# project2.net
KiCad netlist of a schematic drawn in EAGLE
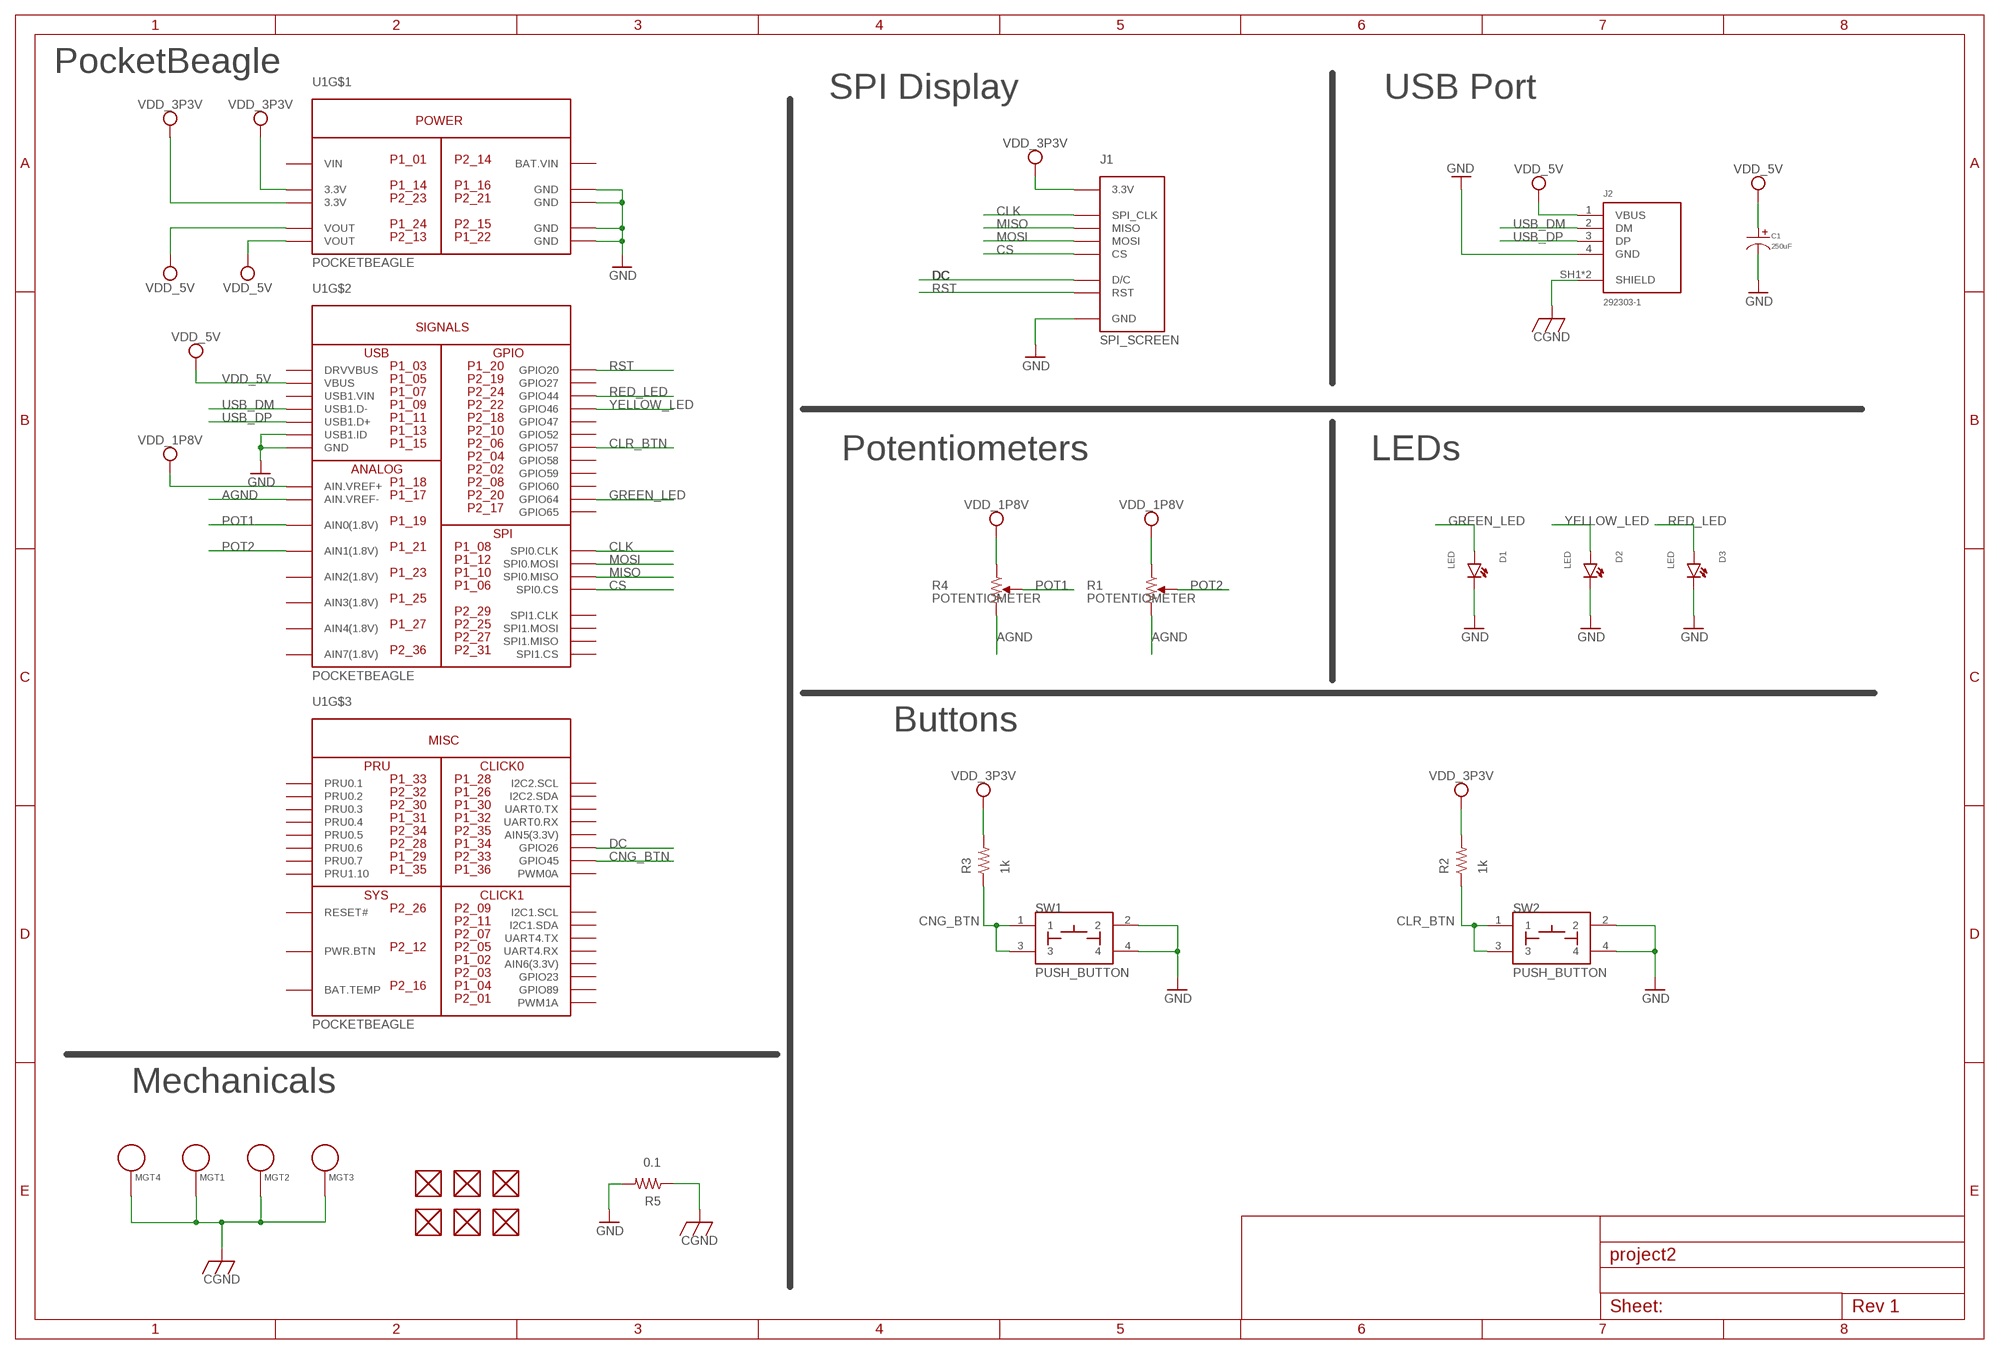
[diagram p0: schematic, sheet 1]

(export (version "E")
  (design (tool "Eeschema 10.0.6"))
  (components
    (comp (ref "C1")
      (value "250uF")
      (footprint "eagle-import:CP10MM")
      (libsource (lib "eagle-import") (part "CAPACITOR_P_10MM"))
    )
    (comp (ref "D1")
      (value "LED")
      (footprint "eagle-import:EIA-STD")
      (libsource (lib "eagle-import") (part "LED"))
    )
    (comp (ref "D2")
      (value "LED")
      (footprint "eagle-import:EIA-STD")
      (libsource (lib "eagle-import") (part "LED"))
    )
    (comp (ref "D3")
      (value "LED")
      (footprint "eagle-import:EIA-STD")
      (libsource (lib "eagle-import") (part "LED"))
    )
    (comp (ref "FUD1")
      (value "FIDUCIAL")
      (footprint "eagle-import:FIDUCIAL_40MIL")
      (libsource (lib "eagle-import") (part "FIDUCIAL"))
    )
    (comp (ref "FUD2")
      (value "FIDUCIAL")
      (footprint "eagle-import:FIDUCIAL_40MIL")
      (libsource (lib "eagle-import") (part "FIDUCIAL"))
    )
    (comp (ref "FUD3")
      (value "FIDUCIAL")
      (footprint "eagle-import:FIDUCIAL_40MIL")
      (libsource (lib "eagle-import") (part "FIDUCIAL"))
    )
    (comp (ref "FUD4")
      (value "FIDUCIAL")
      (footprint "eagle-import:FIDUCIAL_40MIL")
      (libsource (lib "eagle-import") (part "FIDUCIAL"))
    )
    (comp (ref "FUD5")
      (value "FIDUCIAL")
      (footprint "eagle-import:FIDUCIAL_40MIL")
      (libsource (lib "eagle-import") (part "FIDUCIAL"))
    )
    (comp (ref "FUD6")
      (value "FIDUCIAL")
      (footprint "eagle-import:FIDUCIAL_40MIL")
      (libsource (lib "eagle-import") (part "FIDUCIAL"))
    )
    (comp (ref "J1")
      (value "SPI_SCREEN")
      (footprint "eagle-import:SPI_SCREEN")
      (libsource (lib "eagle-import") (part "SPI_SCREEN"))
    )
    (comp (ref "J2")
      (value "292303-1")
      (footprint "eagle-import:TE_292303-1")
      (fields (field (name "MF") "TE Connectivity"))
      (libsource (lib "eagle-import") (part "292303-1"))
    )
    (comp (ref "MGT1")
      (value "MOUNTING_HOLE")
      (footprint "eagle-import:MOUNTING_HOLE")
      (libsource (lib "eagle-import") (part "MOUNTING_HOLE"))
    )
    (comp (ref "MGT2")
      (value "MOUNTING_HOLE")
      (footprint "eagle-import:MOUNTING_HOLE")
      (libsource (lib "eagle-import") (part "MOUNTING_HOLE"))
    )
    (comp (ref "MGT3")
      (value "MOUNTING_HOLE")
      (footprint "eagle-import:MOUNTING_HOLE")
      (libsource (lib "eagle-import") (part "MOUNTING_HOLE"))
    )
    (comp (ref "MGT4")
      (value "MOUNTING_HOLE")
      (footprint "eagle-import:MOUNTING_HOLE")
      (libsource (lib "eagle-import") (part "MOUNTING_HOLE"))
    )
    (comp (ref "R1")
      (value "POTENTIOMETER")
      (footprint "eagle-import:POT-PO90S")
      (libsource (lib "eagle-import") (part "POTENTIOMETER"))
    )
    (comp (ref "R2")
      (value "1k")
      (footprint "eagle-import:R0603")
      (libsource (lib "eagle-import") (part "R_R0603"))
    )
    (comp (ref "R3")
      (value "1k")
      (footprint "eagle-import:R0603")
      (libsource (lib "eagle-import") (part "R_R0603"))
    )
    (comp (ref "R4")
      (value "POTENTIOMETER")
      (footprint "eagle-import:POT-PO90S")
      (libsource (lib "eagle-import") (part "POTENTIOMETER"))
    )
    (comp (ref "R5")
      (value "0.1")
      (footprint "eagle-import:R0603")
      (libsource (lib "eagle-import") (part "R_R0603"))
    )
    (comp (ref "SW1")
      (value "PUSH_BUTTON")
      (footprint "eagle-import:BUTTON_12.5MM")
      (libsource (lib "eagle-import") (part "PUSH_BUTTON"))
    )
    (comp (ref "SW2")
      (value "PUSH_BUTTON")
      (footprint "eagle-import:BUTTON_12.5MM")
      (libsource (lib "eagle-import") (part "PUSH_BUTTON"))
    )
    (comp (ref "U1")
      (value "POCKETBEAGLE")
      (footprint "eagle-import:POCKETBEAGLE")
      (libsource (lib "eagle-import") (part "POCKETBEAGLE"))
    )
  )
  (nets
    (net (code "1") (name "/AGND") (class "Default")
      (node (ref "R1") (pin "CW") (pinfunction "CW_CW") (pintype "passive"))
      (node (ref "R4") (pin "CW") (pinfunction "CW_CW") (pintype "passive"))
      (node (ref "U1") (pin "17@P1") (pinfunction "AIN.VREF-_17@P1") (pintype "input"))
    )
    (net (code "2") (name "/BAT.VIN") (class "Default")
      (node (ref "U1") (pin "14@P2") (pinfunction "BAT.VIN_14@P2") (pintype "power_in"))
    )
    (net (code "3") (name "/CLK") (class "Default")
      (node (ref "J1") (pin "4@JP2") (pinfunction "SPI_CLK_4@JP2") (pintype "bidirectional"))
      (node (ref "U1") (pin "8@P1") (pinfunction "SPI0.CLK_8@P1") (pintype "bidirectional"))
    )
    (net (code "4") (name "/CLR_BTN") (class "Default")
      (node (ref "R2") (pin "1") (pinfunction "1_1") (pintype "passive"))
      (node (ref "SW2") (pin "1") (pinfunction "1_1") (pintype "bidirectional"))
      (node (ref "SW2") (pin "3") (pinfunction "3_3") (pintype "bidirectional"))
      (node (ref "U1") (pin "6@P2") (pinfunction "GPIO57_6@P2") (pintype "bidirectional"))
    )
    (net (code "5") (name "/CNG_BTN") (class "Default")
      (node (ref "R3") (pin "1") (pinfunction "1_1") (pintype "passive"))
      (node (ref "SW1") (pin "1") (pinfunction "1_1") (pintype "bidirectional"))
      (node (ref "SW1") (pin "3") (pinfunction "3_3") (pintype "bidirectional"))
      (node (ref "U1") (pin "33@P2") (pinfunction "GPIO45_33@P2") (pintype "bidirectional"))
    )
    (net (code "6") (name "/CS") (class "Default")
      (node (ref "J1") (pin "7@JP2") (pinfunction "CS_7@JP2") (pintype "bidirectional"))
      (node (ref "U1") (pin "6@P1") (pinfunction "SPI0.CS_6@P1") (pintype "bidirectional"))
    )
    (net (code "7") (name "/DC") (class "Default")
      (node (ref "J1") (pin "8@JP2") (pinfunction "D/C_8@JP2") (pintype "bidirectional"))
      (node (ref "U1") (pin "34@P1") (pinfunction "GPIO26_34@P1") (pintype "bidirectional"))
    )
    (net (code "8") (name "/GREEN_LED") (class "Default")
      (node (ref "D1") (pin "ANODE") (pinfunction "ANODE_ANODE") (pintype "bidirectional"))
      (node (ref "U1") (pin "20@P2") (pinfunction "GPIO64_20@P2") (pintype "bidirectional"))
    )
    (net (code "9") (name "/MISO") (class "Default")
      (node (ref "J1") (pin "5@JP2") (pinfunction "MISO_5@JP2") (pintype "bidirectional"))
      (node (ref "U1") (pin "10@P1") (pinfunction "SPI0.MISO_10@P1") (pintype "bidirectional"))
    )
    (net (code "10") (name "/MOSI") (class "Default")
      (node (ref "J1") (pin "6@JP2") (pinfunction "MOSI_6@JP2") (pintype "bidirectional"))
      (node (ref "U1") (pin "12@P1") (pinfunction "SPI0.MOSI_12@P1") (pintype "bidirectional"))
    )
    (net (code "11") (name "/POT1") (class "Default")
      (node (ref "R4") (pin "S") (pinfunction "S_S") (pintype "bidirectional"))
      (node (ref "U1") (pin "19@P1") (pinfunction "AIN0(1.8V)_19@P1") (pintype "input"))
    )
    (net (code "12") (name "/POT2") (class "Default")
      (node (ref "R1") (pin "S") (pinfunction "S_S") (pintype "bidirectional"))
      (node (ref "U1") (pin "21@P1") (pinfunction "AIN1(1.8V)_21@P1") (pintype "input"))
    )
    (net (code "13") (name "/RED_LED") (class "Default")
      (node (ref "D3") (pin "ANODE") (pinfunction "ANODE_ANODE") (pintype "bidirectional"))
      (node (ref "U1") (pin "24@P2") (pinfunction "GPIO44_24@P2") (pintype "bidirectional"))
    )
    (net (code "14") (name "/RST") (class "Default")
      (node (ref "J1") (pin "9@JP2") (pinfunction "RST_9@JP2") (pintype "bidirectional"))
      (node (ref "U1") (pin "20@P1") (pinfunction "GPIO20_20@P1") (pintype "bidirectional"))
    )
    (net (code "15") (name "/USB_DM") (class "Default")
      (node (ref "J2") (pin "2") (pinfunction "DM_2") (pintype "passive"))
      (node (ref "U1") (pin "9@P1") (pinfunction "USB1.D-_9@P1") (pintype "bidirectional"))
    )
    (net (code "16") (name "/USB_DP") (class "Default")
      (node (ref "J2") (pin "3") (pinfunction "DP_3") (pintype "passive"))
      (node (ref "U1") (pin "11@P1") (pinfunction "USB1.D+_11@P1") (pintype "bidirectional"))
    )
    (net (code "17") (name "/VIN") (class "Default")
      (node (ref "U1") (pin "1@P1") (pinfunction "VIN_1@P1") (pintype "power_in"))
    )
    (net (code "18") (name "/YELLOW_LED") (class "Default")
      (node (ref "D2") (pin "ANODE") (pinfunction "ANODE_ANODE") (pintype "bidirectional"))
      (node (ref "U1") (pin "22@P2") (pinfunction "GPIO46_22@P2") (pintype "bidirectional"))
    )
    (net (code "19") (name "CGND") (class "Default")
      (node (ref "J2") (pin "SH1") (pinfunction "SHIELD_SH1") (pintype "passive"))
      (node (ref "J2") (pin "SH2") (pinfunction "SHIELD_SH2") (pintype "passive"))
      (node (ref "MGT1") (pin "P$1") (pinfunction "P$1_P$1") (pintype "bidirectional"))
      (node (ref "MGT2") (pin "P$1") (pinfunction "P$1_P$1") (pintype "bidirectional"))
      (node (ref "MGT3") (pin "P$1") (pinfunction "P$1_P$1") (pintype "bidirectional"))
      (node (ref "MGT4") (pin "P$1") (pinfunction "P$1_P$1") (pintype "bidirectional"))
      (node (ref "R5") (pin "1") (pinfunction "1_1") (pintype "passive"))
    )
    (net (code "20") (name "GND") (class "Default")
      (node (ref "C1") (pin "P$2") (pinfunction "P$2_P$2") (pintype "passive"))
      (node (ref "D1") (pin "CATHODE") (pinfunction "CATHODE_CATHODE") (pintype "bidirectional"))
      (node (ref "D2") (pin "CATHODE") (pinfunction "CATHODE_CATHODE") (pintype "bidirectional"))
      (node (ref "D3") (pin "CATHODE") (pinfunction "CATHODE_CATHODE") (pintype "bidirectional"))
      (node (ref "J1") (pin "1@JP2") (pinfunction "GND_1@JP2") (pintype "bidirectional"))
      (node (ref "J2") (pin "4") (pinfunction "GND_4") (pintype "passive"))
      (node (ref "R5") (pin "2") (pinfunction "2_2") (pintype "passive"))
      (node (ref "SW1") (pin "2") (pinfunction "2_2") (pintype "bidirectional"))
      (node (ref "SW1") (pin "4") (pinfunction "4_4") (pintype "bidirectional"))
      (node (ref "SW2") (pin "2") (pinfunction "2_2") (pintype "bidirectional"))
      (node (ref "SW2") (pin "4") (pinfunction "4_4") (pintype "bidirectional"))
      (node (ref "U1") (pin "13@P1") (pinfunction "USB1.ID_13@P1") (pintype "bidirectional"))
      (node (ref "U1") (pin "15@P1") (pinfunction "GND_15@P1") (pintype "bidirectional"))
      (node (ref "U1") (pin "15@P2") (pinfunction "GND_15@P2") (pintype "power_in"))
      (node (ref "U1") (pin "16@P1") (pinfunction "GND_16@P1") (pintype "power_in"))
      (node (ref "U1") (pin "21@P2") (pinfunction "GND_21@P2") (pintype "power_in"))
      (node (ref "U1") (pin "22@P1") (pinfunction "GND_22@P1") (pintype "power_in"))
    )
    (net (code "21") (name "VDD_1P8V") (class "Default")
      (node (ref "R1") (pin "CCW") (pinfunction "CCW_CCW") (pintype "passive"))
      (node (ref "R4") (pin "CCW") (pinfunction "CCW_CCW") (pintype "passive"))
      (node (ref "U1") (pin "18@P1") (pinfunction "AIN.VREF+_18@P1") (pintype "input"))
    )
    (net (code "22") (name "VDD_3P3V") (class "Default")
      (node (ref "J1") (pin "3@JP2") (pinfunction "3.3V_3@JP2") (pintype "bidirectional"))
      (node (ref "R2") (pin "2") (pinfunction "2_2") (pintype "passive"))
      (node (ref "R3") (pin "2") (pinfunction "2_2") (pintype "passive"))
      (node (ref "U1") (pin "14@P1") (pinfunction "3.3V_14@P1") (pintype "power_in"))
      (node (ref "U1") (pin "23@P2") (pinfunction "3.3V_23@P2") (pintype "power_in"))
    )
    (net (code "23") (name "VDD_5V") (class "Default")
      (node (ref "C1") (pin "P$1") (pinfunction "P$1_P$1") (pintype "passive"))
      (node (ref "J2") (pin "1") (pinfunction "VBUS_1") (pintype "passive"))
      (node (ref "U1") (pin "13@P2") (pinfunction "VOUT_13@P2") (pintype "power_in"))
      (node (ref "U1") (pin "24@P1") (pinfunction "VOUT_24@P1") (pintype "power_in"))
      (node (ref "U1") (pin "5@P1") (pinfunction "VBUS_5@P1") (pintype "bidirectional"))
    )
    (net (code "24") (name "unconnected-(FUD1-PadP$1)") (class "Default")
      (node (ref "FUD1") (pin "P$1") (pinfunction "P$1_P$1") (pintype "no_connect"))
    )
    (net (code "25") (name "unconnected-(FUD2-PadP$1)") (class "Default")
      (node (ref "FUD2") (pin "P$1") (pinfunction "P$1_P$1") (pintype "no_connect"))
    )
    (net (code "26") (name "unconnected-(FUD3-PadP$1)") (class "Default")
      (node (ref "FUD3") (pin "P$1") (pinfunction "P$1_P$1") (pintype "no_connect"))
    )
    (net (code "27") (name "unconnected-(FUD4-PadP$1)") (class "Default")
      (node (ref "FUD4") (pin "P$1") (pinfunction "P$1_P$1") (pintype "no_connect"))
    )
    (net (code "28") (name "unconnected-(FUD5-PadP$1)") (class "Default")
      (node (ref "FUD5") (pin "P$1") (pinfunction "P$1_P$1") (pintype "no_connect"))
    )
    (net (code "29") (name "unconnected-(FUD6-PadP$1)") (class "Default")
      (node (ref "FUD6") (pin "P$1") (pinfunction "P$1_P$1") (pintype "no_connect"))
    )
    (net (code "30") (name "unconnected-(U1B-AIN2(1.8V)-Pad23@P1)") (class "Default")
      (node (ref "U1") (pin "23@P1") (pinfunction "AIN2(1.8V)_23@P1") (pintype "input"))
    )
    (net (code "31") (name "unconnected-(U1B-AIN3(1.8V)-Pad25@P1)") (class "Default")
      (node (ref "U1") (pin "25@P1") (pinfunction "AIN3(1.8V)_25@P1") (pintype "input"))
    )
    (net (code "32") (name "unconnected-(U1B-AIN4(1.8V)-Pad27@P1)") (class "Default")
      (node (ref "U1") (pin "27@P1") (pinfunction "AIN4(1.8V)_27@P1") (pintype "input"))
    )
    (net (code "33") (name "unconnected-(U1B-AIN7(1.8V)-Pad36@P2)") (class "Default")
      (node (ref "U1") (pin "36@P2") (pinfunction "AIN7(1.8V)_36@P2") (pintype "input"))
    )
    (net (code "34") (name "unconnected-(U1B-DRVVBUS-Pad3@P1)") (class "Default")
      (node (ref "U1") (pin "3@P1") (pinfunction "DRVVBUS_3@P1") (pintype "bidirectional"))
    )
    (net (code "35") (name "unconnected-(U1B-GPIO27-Pad19@P2)") (class "Default")
      (node (ref "U1") (pin "19@P2") (pinfunction "GPIO27_19@P2") (pintype "bidirectional"))
    )
    (net (code "36") (name "unconnected-(U1B-GPIO47-Pad18@P2)") (class "Default")
      (node (ref "U1") (pin "18@P2") (pinfunction "GPIO47_18@P2") (pintype "bidirectional"))
    )
    (net (code "37") (name "unconnected-(U1B-GPIO52-Pad10@P2)") (class "Default")
      (node (ref "U1") (pin "10@P2") (pinfunction "GPIO52_10@P2") (pintype "bidirectional"))
    )
    (net (code "38") (name "unconnected-(U1B-GPIO58-Pad4@P2)") (class "Default")
      (node (ref "U1") (pin "4@P2") (pinfunction "GPIO58_4@P2") (pintype "bidirectional"))
    )
    (net (code "39") (name "unconnected-(U1B-GPIO59-Pad2@P2)") (class "Default")
      (node (ref "U1") (pin "2@P2") (pinfunction "GPIO59_2@P2") (pintype "bidirectional"))
    )
    (net (code "40") (name "unconnected-(U1B-GPIO60-Pad8@P2)") (class "Default")
      (node (ref "U1") (pin "8@P2") (pinfunction "GPIO60_8@P2") (pintype "bidirectional"))
    )
    (net (code "41") (name "unconnected-(U1B-GPIO65-Pad17@P2)") (class "Default")
      (node (ref "U1") (pin "17@P2") (pinfunction "GPIO65_17@P2") (pintype "bidirectional"))
    )
    (net (code "42") (name "unconnected-(U1B-SPI1.CLK-Pad29@P2)") (class "Default")
      (node (ref "U1") (pin "29@P2") (pinfunction "SPI1.CLK_29@P2") (pintype "bidirectional"))
    )
    (net (code "43") (name "unconnected-(U1B-SPI1.CS-Pad31@P2)") (class "Default")
      (node (ref "U1") (pin "31@P2") (pinfunction "SPI1.CS_31@P2") (pintype "bidirectional"))
    )
    (net (code "44") (name "unconnected-(U1B-SPI1.MISO-Pad27@P2)") (class "Default")
      (node (ref "U1") (pin "27@P2") (pinfunction "SPI1.MISO_27@P2") (pintype "bidirectional"))
    )
    (net (code "45") (name "unconnected-(U1B-SPI1.MOSI-Pad25@P2)") (class "Default")
      (node (ref "U1") (pin "25@P2") (pinfunction "SPI1.MOSI_25@P2") (pintype "bidirectional"))
    )
    (net (code "46") (name "unconnected-(U1B-USB1.VIN-Pad7@P1)") (class "Default")
      (node (ref "U1") (pin "7@P1") (pinfunction "USB1.VIN_7@P1") (pintype "bidirectional"))
    )
    (net (code "47") (name "unconnected-(U1C-AIN5(3.3V)-Pad35@P2)") (class "Default")
      (node (ref "U1") (pin "35@P2") (pinfunction "AIN5(3.3V)_35@P2") (pintype "bidirectional"))
    )
    (net (code "48") (name "unconnected-(U1C-AIN6(3.3V)-Pad2@P1)") (class "Default")
      (node (ref "U1") (pin "2@P1") (pinfunction "AIN6(3.3V)_2@P1") (pintype "bidirectional"))
    )
    (net (code "49") (name "unconnected-(U1C-BAT.TEMP-Pad16@P2)") (class "Default")
      (node (ref "U1") (pin "16@P2") (pinfunction "BAT.TEMP_16@P2") (pintype "input"))
    )
    (net (code "50") (name "unconnected-(U1C-GPIO23-Pad3@P2)") (class "Default")
      (node (ref "U1") (pin "3@P2") (pinfunction "GPIO23_3@P2") (pintype "bidirectional"))
    )
    (net (code "51") (name "unconnected-(U1C-GPIO89-Pad4@P1)") (class "Default")
      (node (ref "U1") (pin "4@P1") (pinfunction "GPIO89_4@P1") (pintype "bidirectional"))
    )
    (net (code "52") (name "unconnected-(U1C-I2C1.SCL-Pad9@P2)") (class "Default")
      (node (ref "U1") (pin "9@P2") (pinfunction "I2C1.SCL_9@P2") (pintype "bidirectional"))
    )
    (net (code "53") (name "unconnected-(U1C-I2C1.SDA-Pad11@P2)") (class "Default")
      (node (ref "U1") (pin "11@P2") (pinfunction "I2C1.SDA_11@P2") (pintype "bidirectional"))
    )
    (net (code "54") (name "unconnected-(U1C-I2C2.SCL-Pad28@P1)") (class "Default")
      (node (ref "U1") (pin "28@P1") (pinfunction "I2C2.SCL_28@P1") (pintype "bidirectional"))
    )
    (net (code "55") (name "unconnected-(U1C-I2C2.SDA-Pad26@P1)") (class "Default")
      (node (ref "U1") (pin "26@P1") (pinfunction "I2C2.SDA_26@P1") (pintype "bidirectional"))
    )
    (net (code "56") (name "unconnected-(U1C-PRU0.1-Pad33@P1)") (class "Default")
      (node (ref "U1") (pin "33@P1") (pinfunction "PRU0.1_33@P1") (pintype "bidirectional"))
    )
    (net (code "57") (name "unconnected-(U1C-PRU0.2-Pad32@P2)") (class "Default")
      (node (ref "U1") (pin "32@P2") (pinfunction "PRU0.2_32@P2") (pintype "bidirectional"))
    )
    (net (code "58") (name "unconnected-(U1C-PRU0.3-Pad30@P2)") (class "Default")
      (node (ref "U1") (pin "30@P2") (pinfunction "PRU0.3_30@P2") (pintype "bidirectional"))
    )
    (net (code "59") (name "unconnected-(U1C-PRU0.4-Pad31@P1)") (class "Default")
      (node (ref "U1") (pin "31@P1") (pinfunction "PRU0.4_31@P1") (pintype "bidirectional"))
    )
    (net (code "60") (name "unconnected-(U1C-PRU0.5-Pad34@P2)") (class "Default")
      (node (ref "U1") (pin "34@P2") (pinfunction "PRU0.5_34@P2") (pintype "bidirectional"))
    )
    (net (code "61") (name "unconnected-(U1C-PRU0.6-Pad28@P2)") (class "Default")
      (node (ref "U1") (pin "28@P2") (pinfunction "PRU0.6_28@P2") (pintype "bidirectional"))
    )
    (net (code "62") (name "unconnected-(U1C-PRU0.7-Pad29@P1)") (class "Default")
      (node (ref "U1") (pin "29@P1") (pinfunction "PRU0.7_29@P1") (pintype "bidirectional"))
    )
    (net (code "63") (name "unconnected-(U1C-PRU1.10-Pad35@P1)") (class "Default")
      (node (ref "U1") (pin "35@P1") (pinfunction "PRU1.10_35@P1") (pintype "bidirectional"))
    )
    (net (code "64") (name "unconnected-(U1C-PWM0A-Pad36@P1)") (class "Default")
      (node (ref "U1") (pin "36@P1") (pinfunction "PWM0A_36@P1") (pintype "bidirectional"))
    )
    (net (code "65") (name "unconnected-(U1C-PWM1A-Pad1@P2)") (class "Default")
      (node (ref "U1") (pin "1@P2") (pinfunction "PWM1A_1@P2") (pintype "bidirectional"))
    )
    (net (code "66") (name "unconnected-(U1C-PWR.BTN-Pad12@P2)") (class "Default")
      (node (ref "U1") (pin "12@P2") (pinfunction "PWR.BTN_12@P2") (pintype "input"))
    )
    (net (code "67") (name "unconnected-(U1C-RESET#-Pad26@P2)") (class "Default")
      (node (ref "U1") (pin "26@P2") (pinfunction "RESET#_26@P2") (pintype "input"))
    )
    (net (code "68") (name "unconnected-(U1C-UART0.RX-Pad32@P1)") (class "Default")
      (node (ref "U1") (pin "32@P1") (pinfunction "UART0.RX_32@P1") (pintype "bidirectional"))
    )
    (net (code "69") (name "unconnected-(U1C-UART0.TX-Pad30@P1)") (class "Default")
      (node (ref "U1") (pin "30@P1") (pinfunction "UART0.TX_30@P1") (pintype "bidirectional"))
    )
    (net (code "70") (name "unconnected-(U1C-UART4.RX-Pad5@P2)") (class "Default")
      (node (ref "U1") (pin "5@P2") (pinfunction "UART4.RX_5@P2") (pintype "bidirectional"))
    )
    (net (code "71") (name "unconnected-(U1C-UART4.TX-Pad7@P2)") (class "Default")
      (node (ref "U1") (pin "7@P2") (pinfunction "UART4.TX_7@P2") (pintype "bidirectional"))
    )
  )
)
